# Input2.net
KiCad netlist of a schematic drawn in Altium Designer
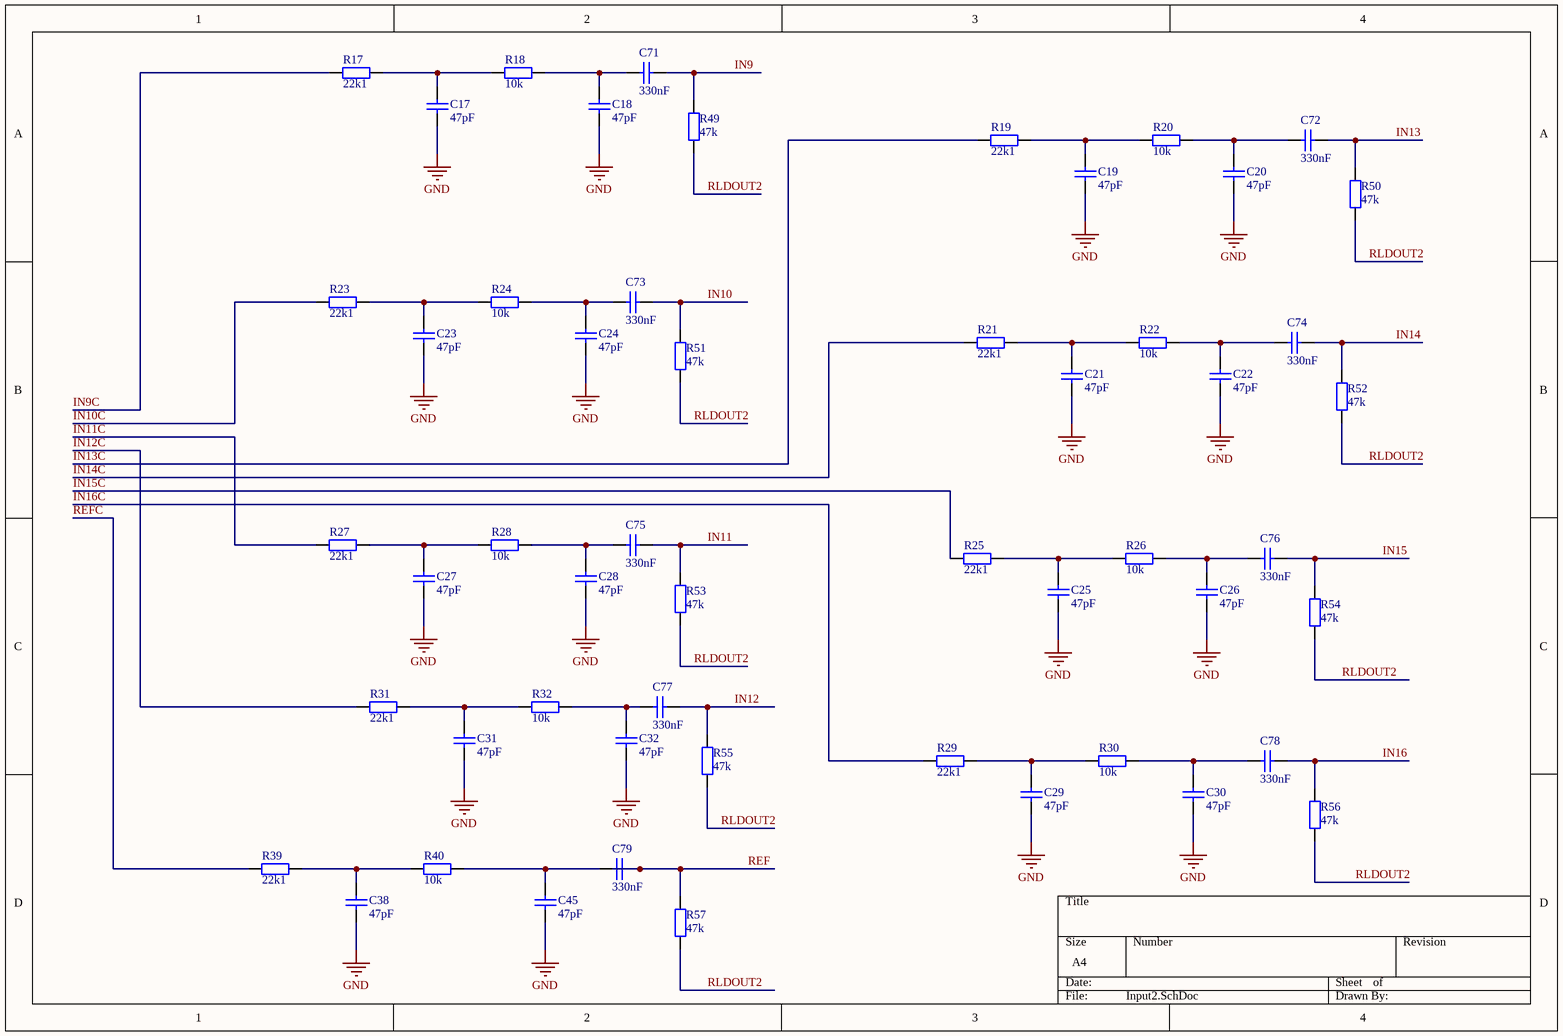
[diagram p0: Input2.SchDoc]

(export (version "E")
  (design (tool "Eeschema 10.0.6"))
  (components
    (comp (ref "C17")
      (value "47pF")
      (footprint "RESC1608X50N")
      (description "Capacitor")
      (fields (field (name "PUBLISHER") "Altium Limited"))
      (libsource (lib "Miscellaneous Devices") (part "Cap"))
    )
    (comp (ref "C18")
      (value "47pF")
      (footprint "RESC1608X50N")
      (description "Capacitor")
      (fields (field (name "PUBLISHER") "Altium Limited"))
      (libsource (lib "Miscellaneous Devices") (part "Cap"))
    )
    (comp (ref "C19")
      (value "47pF")
      (footprint "RESC1608X50N")
      (description "Capacitor")
      (fields (field (name "PUBLISHER") "Altium Limited"))
      (libsource (lib "Miscellaneous Devices") (part "Cap"))
    )
    (comp (ref "C20")
      (value "47pF")
      (footprint "RESC1608X50N")
      (description "Capacitor")
      (fields (field (name "PUBLISHER") "Altium Limited"))
      (libsource (lib "Miscellaneous Devices") (part "Cap"))
    )
    (comp (ref "C21")
      (value "47pF")
      (footprint "RESC1608X50N")
      (description "Capacitor")
      (fields (field (name "PUBLISHER") "Altium Limited"))
      (libsource (lib "Miscellaneous Devices") (part "Cap"))
    )
    (comp (ref "C22")
      (value "47pF")
      (footprint "RESC1608X50N")
      (description "Capacitor")
      (fields (field (name "PUBLISHER") "Altium Limited"))
      (libsource (lib "Miscellaneous Devices") (part "Cap"))
    )
    (comp (ref "C23")
      (value "47pF")
      (footprint "RESC1608X50N")
      (description "Capacitor")
      (fields (field (name "PUBLISHER") "Altium Limited"))
      (libsource (lib "Miscellaneous Devices") (part "Cap"))
    )
    (comp (ref "C24")
      (value "47pF")
      (footprint "RESC1608X50N")
      (description "Capacitor")
      (fields (field (name "PUBLISHER") "Altium Limited"))
      (libsource (lib "Miscellaneous Devices") (part "Cap"))
    )
    (comp (ref "C25")
      (value "47pF")
      (footprint "RESC1608X50N")
      (description "Capacitor")
      (fields (field (name "PUBLISHER") "Altium Limited"))
      (libsource (lib "Miscellaneous Devices") (part "Cap"))
    )
    (comp (ref "C26")
      (value "47pF")
      (footprint "RESC1608X50N")
      (description "Capacitor")
      (fields (field (name "PUBLISHER") "Altium Limited"))
      (libsource (lib "Miscellaneous Devices") (part "Cap"))
    )
    (comp (ref "C27")
      (value "47pF")
      (footprint "RESC1608X50N")
      (description "Capacitor")
      (fields (field (name "PUBLISHER") "Altium Limited"))
      (libsource (lib "Miscellaneous Devices") (part "Cap"))
    )
    (comp (ref "C28")
      (value "47pF")
      (footprint "RESC1608X50N")
      (description "Capacitor")
      (fields (field (name "PUBLISHER") "Altium Limited"))
      (libsource (lib "Miscellaneous Devices") (part "Cap"))
    )
    (comp (ref "C29")
      (value "47pF")
      (footprint "RESC1608X50N")
      (description "Capacitor")
      (fields (field (name "PUBLISHER") "Altium Limited"))
      (libsource (lib "Miscellaneous Devices") (part "Cap"))
    )
    (comp (ref "C30")
      (value "47pF")
      (footprint "RESC1608X50N")
      (description "Capacitor")
      (fields (field (name "PUBLISHER") "Altium Limited"))
      (libsource (lib "Miscellaneous Devices") (part "Cap"))
    )
    (comp (ref "C31")
      (value "47pF")
      (footprint "RESC1608X50N")
      (description "Capacitor")
      (fields (field (name "PUBLISHER") "Altium Limited"))
      (libsource (lib "Miscellaneous Devices") (part "Cap"))
    )
    (comp (ref "C32")
      (value "47pF")
      (footprint "RESC1608X50N")
      (description "Capacitor")
      (fields (field (name "PUBLISHER") "Altium Limited"))
      (libsource (lib "Miscellaneous Devices") (part "Cap"))
    )
    (comp (ref "C38")
      (value "47pF")
      (footprint "RESC1608X50N")
      (description "Capacitor")
      (fields (field (name "PUBLISHER") "Altium Limited"))
      (libsource (lib "Miscellaneous Devices") (part "Cap"))
    )
    (comp (ref "C45")
      (value "47pF")
      (footprint "RESC1608X50N")
      (description "Capacitor")
      (fields (field (name "PUBLISHER") "Altium Limited"))
      (libsource (lib "Miscellaneous Devices") (part "Cap"))
    )
    (comp (ref "C71")
      (value "330nF")
      (footprint "RESC1608X50N")
      (description "Capacitor")
      (fields (field (name "PUBLISHER") "Altium Limited"))
      (libsource (lib "Miscellaneous Devices") (part "Cap"))
    )
    (comp (ref "C72")
      (value "330nF")
      (footprint "RESC1608X50N")
      (description "Capacitor")
      (fields (field (name "PUBLISHER") "Altium Limited"))
      (libsource (lib "Miscellaneous Devices") (part "Cap"))
    )
    (comp (ref "C73")
      (value "330nF")
      (footprint "RESC1608X50N")
      (description "Capacitor")
      (fields (field (name "PUBLISHER") "Altium Limited"))
      (libsource (lib "Miscellaneous Devices") (part "Cap"))
    )
    (comp (ref "C74")
      (value "330nF")
      (footprint "RESC1608X50N")
      (description "Capacitor")
      (fields (field (name "PUBLISHER") "Altium Limited"))
      (libsource (lib "Miscellaneous Devices") (part "Cap"))
    )
    (comp (ref "C75")
      (value "330nF")
      (footprint "RESC1608X50N")
      (description "Capacitor")
      (fields (field (name "PUBLISHER") "Altium Limited"))
      (libsource (lib "Miscellaneous Devices") (part "Cap"))
    )
    (comp (ref "C76")
      (value "330nF")
      (footprint "RESC1608X50N")
      (description "Capacitor")
      (fields (field (name "PUBLISHER") "Altium Limited"))
      (libsource (lib "Miscellaneous Devices") (part "Cap"))
    )
    (comp (ref "C77")
      (value "330nF")
      (footprint "RESC1608X50N")
      (description "Capacitor")
      (fields (field (name "PUBLISHER") "Altium Limited"))
      (libsource (lib "Miscellaneous Devices") (part "Cap"))
    )
    (comp (ref "C78")
      (value "330nF")
      (footprint "RESC1608X50N")
      (description "Capacitor")
      (fields (field (name "PUBLISHER") "Altium Limited"))
      (libsource (lib "Miscellaneous Devices") (part "Cap"))
    )
    (comp (ref "C79")
      (value "330nF")
      (footprint "RESC1608X50N")
      (description "Capacitor")
      (fields (field (name "PUBLISHER") "Altium Limited"))
      (libsource (lib "Miscellaneous Devices") (part "Cap"))
    )
    (comp (ref "R17")
      (value "22k1")
      (footprint "CAPC1608X90")
      (description "Resistor")
      (fields (field (name "PUBLISHER") "Altium Limited"))
      (libsource (lib "") (part "Res2_1"))
    )
    (comp (ref "R18")
      (value "10k")
      (footprint "CAPC1608X90")
      (description "Resistor")
      (fields (field (name "PUBLISHER") "Altium Limited"))
      (libsource (lib "") (part "Res2_1"))
    )
    (comp (ref "R19")
      (value "22k1")
      (footprint "CAPC1608X90")
      (description "Resistor")
      (fields (field (name "PUBLISHER") "Altium Limited"))
      (libsource (lib "") (part "Res2_1"))
    )
    (comp (ref "R20")
      (value "10k")
      (footprint "CAPC1608X90")
      (description "Resistor")
      (fields (field (name "PUBLISHER") "Altium Limited"))
      (libsource (lib "") (part "Res2_1"))
    )
    (comp (ref "R21")
      (value "22k1")
      (footprint "CAPC1608X90")
      (description "Resistor")
      (fields (field (name "PUBLISHER") "Altium Limited"))
      (libsource (lib "") (part "Res2_1"))
    )
    (comp (ref "R22")
      (value "10k")
      (footprint "CAPC1608X90")
      (description "Resistor")
      (fields (field (name "PUBLISHER") "Altium Limited"))
      (libsource (lib "") (part "Res2_1"))
    )
    (comp (ref "R23")
      (value "22k1")
      (footprint "CAPC1608X90")
      (description "Resistor")
      (fields (field (name "PUBLISHER") "Altium Limited"))
      (libsource (lib "") (part "Res2_1"))
    )
    (comp (ref "R24")
      (value "10k")
      (footprint "CAPC1608X90")
      (description "Resistor")
      (fields (field (name "PUBLISHER") "Altium Limited"))
      (libsource (lib "") (part "Res2_1"))
    )
    (comp (ref "R25")
      (value "22k1")
      (footprint "CAPC1608X90")
      (description "Resistor")
      (fields (field (name "PUBLISHER") "Altium Limited"))
      (libsource (lib "") (part "Res2_1"))
    )
    (comp (ref "R26")
      (value "10k")
      (footprint "CAPC1608X90")
      (description "Resistor")
      (fields (field (name "PUBLISHER") "Altium Limited"))
      (libsource (lib "") (part "Res2_1"))
    )
    (comp (ref "R27")
      (value "22k1")
      (footprint "CAPC1608X90")
      (description "Resistor")
      (fields (field (name "PUBLISHER") "Altium Limited"))
      (libsource (lib "") (part "Res2_1"))
    )
    (comp (ref "R28")
      (value "10k")
      (footprint "CAPC1608X90")
      (description "Resistor")
      (fields (field (name "PUBLISHER") "Altium Limited"))
      (libsource (lib "") (part "Res2_1"))
    )
    (comp (ref "R29")
      (value "22k1")
      (footprint "CAPC1608X90")
      (description "Resistor")
      (fields (field (name "PUBLISHER") "Altium Limited"))
      (libsource (lib "") (part "Res2_1"))
    )
    (comp (ref "R30")
      (value "10k")
      (footprint "CAPC1608X90")
      (description "Resistor")
      (fields (field (name "PUBLISHER") "Altium Limited"))
      (libsource (lib "") (part "Res2_1"))
    )
    (comp (ref "R31")
      (value "22k1")
      (footprint "CAPC1608X90")
      (description "Resistor")
      (fields (field (name "PUBLISHER") "Altium Limited"))
      (libsource (lib "") (part "Res2_1"))
    )
    (comp (ref "R32")
      (value "10k")
      (footprint "CAPC1608X90")
      (description "Resistor")
      (fields (field (name "PUBLISHER") "Altium Limited"))
      (libsource (lib "") (part "Res2_1"))
    )
    (comp (ref "R39")
      (value "22k1")
      (footprint "CAPC1608X90")
      (description "Resistor")
      (fields (field (name "PUBLISHER") "Altium Limited"))
      (libsource (lib "") (part "Res2_1"))
    )
    (comp (ref "R40")
      (value "10k")
      (footprint "CAPC1608X90")
      (description "Resistor")
      (fields (field (name "PUBLISHER") "Altium Limited"))
      (libsource (lib "") (part "Res2_1"))
    )
    (comp (ref "R49")
      (value "47k")
      (footprint "CAPC1608X90")
      (description "Resistor")
      (fields (field (name "PUBLISHER") "Altium Limited"))
      (libsource (lib "Miscellaneous Devices") (part "Res2"))
    )
    (comp (ref "R50")
      (value "47k")
      (footprint "CAPC1608X90")
      (description "Resistor")
      (fields (field (name "PUBLISHER") "Altium Limited"))
      (libsource (lib "Miscellaneous Devices") (part "Res2"))
    )
    (comp (ref "R51")
      (value "47k")
      (footprint "CAPC1608X90")
      (description "Resistor")
      (fields (field (name "PUBLISHER") "Altium Limited"))
      (libsource (lib "Miscellaneous Devices") (part "Res2"))
    )
    (comp (ref "R52")
      (value "47k")
      (footprint "CAPC1608X90")
      (description "Resistor")
      (fields (field (name "PUBLISHER") "Altium Limited"))
      (libsource (lib "Miscellaneous Devices") (part "Res2"))
    )
    (comp (ref "R53")
      (value "47k")
      (footprint "CAPC1608X90")
      (description "Resistor")
      (fields (field (name "PUBLISHER") "Altium Limited"))
      (libsource (lib "Miscellaneous Devices") (part "Res2"))
    )
    (comp (ref "R54")
      (value "47k")
      (footprint "CAPC1608X90")
      (description "Resistor")
      (fields (field (name "PUBLISHER") "Altium Limited"))
      (libsource (lib "Miscellaneous Devices") (part "Res2"))
    )
    (comp (ref "R55")
      (value "47k")
      (footprint "CAPC1608X90")
      (description "Resistor")
      (fields (field (name "PUBLISHER") "Altium Limited"))
      (libsource (lib "Miscellaneous Devices") (part "Res2"))
    )
    (comp (ref "R56")
      (value "47k")
      (footprint "CAPC1608X90")
      (description "Resistor")
      (fields (field (name "PUBLISHER") "Altium Limited"))
      (libsource (lib "Miscellaneous Devices") (part "Res2"))
    )
    (comp (ref "R57")
      (value "47k")
      (footprint "CAPC1608X90")
      (description "Resistor")
      (fields (field (name "PUBLISHER") "Altium Limited"))
      (libsource (lib "Miscellaneous Devices") (part "Res2"))
    )
  )
  (nets
    (net (code "1") (name "/IN9") (class "Default")
      (node (ref "C71") (pin "1") (pinfunction "1_1") (pintype "passive"))
      (node (ref "R49") (pin "2") (pinfunction "2_2") (pintype "passive"))
    )
    (net (code "2") (name "/IN9C") (class "Default")
      (node (ref "R17") (pin "1") (pinfunction "1_1") (pintype "passive"))
    )
    (net (code "3") (name "/IN10") (class "Default")
      (node (ref "C73") (pin "1") (pinfunction "1_1") (pintype "passive"))
      (node (ref "R51") (pin "2") (pinfunction "2_2") (pintype "passive"))
    )
    (net (code "4") (name "/IN10C") (class "Default")
      (node (ref "R23") (pin "1") (pinfunction "1_1") (pintype "passive"))
    )
    (net (code "5") (name "/IN11") (class "Default")
      (node (ref "C75") (pin "1") (pinfunction "1_1") (pintype "passive"))
      (node (ref "R53") (pin "2") (pinfunction "2_2") (pintype "passive"))
    )
    (net (code "6") (name "/IN11C") (class "Default")
      (node (ref "R27") (pin "1") (pinfunction "1_1") (pintype "passive"))
    )
    (net (code "7") (name "/IN12") (class "Default")
      (node (ref "C77") (pin "1") (pinfunction "1_1") (pintype "passive"))
      (node (ref "R55") (pin "2") (pinfunction "2_2") (pintype "passive"))
    )
    (net (code "8") (name "/IN12C") (class "Default")
      (node (ref "R31") (pin "1") (pinfunction "1_1") (pintype "passive"))
    )
    (net (code "9") (name "/IN13") (class "Default")
      (node (ref "C72") (pin "1") (pinfunction "1_1") (pintype "passive"))
      (node (ref "R50") (pin "2") (pinfunction "2_2") (pintype "passive"))
    )
    (net (code "10") (name "/IN13C") (class "Default")
      (node (ref "R19") (pin "1") (pinfunction "1_1") (pintype "passive"))
    )
    (net (code "11") (name "/IN14") (class "Default")
      (node (ref "C74") (pin "1") (pinfunction "1_1") (pintype "passive"))
      (node (ref "R52") (pin "2") (pinfunction "2_2") (pintype "passive"))
    )
    (net (code "12") (name "/IN14C") (class "Default")
      (node (ref "R21") (pin "1") (pinfunction "1_1") (pintype "passive"))
    )
    (net (code "13") (name "/IN15") (class "Default")
      (node (ref "C76") (pin "1") (pinfunction "1_1") (pintype "passive"))
      (node (ref "R54") (pin "2") (pinfunction "2_2") (pintype "passive"))
    )
    (net (code "14") (name "/IN15C") (class "Default")
      (node (ref "R25") (pin "1") (pinfunction "1_1") (pintype "passive"))
    )
    (net (code "15") (name "/IN16") (class "Default")
      (node (ref "C78") (pin "1") (pinfunction "1_1") (pintype "passive"))
      (node (ref "R56") (pin "2") (pinfunction "2_2") (pintype "passive"))
    )
    (net (code "16") (name "/IN16C") (class "Default")
      (node (ref "R29") (pin "1") (pinfunction "1_1") (pintype "passive"))
    )
    (net (code "17") (name "/REF") (class "Default")
      (node (ref "C79") (pin "1") (pinfunction "1_1") (pintype "passive"))
      (node (ref "R57") (pin "2") (pinfunction "2_2") (pintype "passive"))
    )
    (net (code "18") (name "/REFC") (class "Default")
      (node (ref "R39") (pin "1") (pinfunction "1_1") (pintype "passive"))
    )
    (net (code "19") (name "/RLDOUT2") (class "Default")
      (node (ref "R49") (pin "1") (pinfunction "1_1") (pintype "passive"))
      (node (ref "R50") (pin "1") (pinfunction "1_1") (pintype "passive"))
      (node (ref "R51") (pin "1") (pinfunction "1_1") (pintype "passive"))
      (node (ref "R52") (pin "1") (pinfunction "1_1") (pintype "passive"))
      (node (ref "R53") (pin "1") (pinfunction "1_1") (pintype "passive"))
      (node (ref "R54") (pin "1") (pinfunction "1_1") (pintype "passive"))
      (node (ref "R55") (pin "1") (pinfunction "1_1") (pintype "passive"))
      (node (ref "R56") (pin "1") (pinfunction "1_1") (pintype "passive"))
      (node (ref "R57") (pin "1") (pinfunction "1_1") (pintype "passive"))
    )
    (net (code "20") (name "GND") (class "Default")
      (node (ref "C17") (pin "1") (pinfunction "1_1") (pintype "passive"))
      (node (ref "C18") (pin "1") (pinfunction "1_1") (pintype "passive"))
      (node (ref "C19") (pin "1") (pinfunction "1_1") (pintype "passive"))
      (node (ref "C20") (pin "1") (pinfunction "1_1") (pintype "passive"))
      (node (ref "C21") (pin "1") (pinfunction "1_1") (pintype "passive"))
      (node (ref "C22") (pin "1") (pinfunction "1_1") (pintype "passive"))
      (node (ref "C23") (pin "1") (pinfunction "1_1") (pintype "passive"))
      (node (ref "C24") (pin "1") (pinfunction "1_1") (pintype "passive"))
      (node (ref "C25") (pin "1") (pinfunction "1_1") (pintype "passive"))
      (node (ref "C26") (pin "1") (pinfunction "1_1") (pintype "passive"))
      (node (ref "C27") (pin "1") (pinfunction "1_1") (pintype "passive"))
      (node (ref "C28") (pin "1") (pinfunction "1_1") (pintype "passive"))
      (node (ref "C29") (pin "1") (pinfunction "1_1") (pintype "passive"))
      (node (ref "C30") (pin "1") (pinfunction "1_1") (pintype "passive"))
      (node (ref "C31") (pin "1") (pinfunction "1_1") (pintype "passive"))
      (node (ref "C32") (pin "1") (pinfunction "1_1") (pintype "passive"))
      (node (ref "C38") (pin "1") (pinfunction "1_1") (pintype "passive"))
      (node (ref "C45") (pin "1") (pinfunction "1_1") (pintype "passive"))
    )
    (net (code "21") (name "Net-(C17-Pad2)") (class "Default")
      (node (ref "C17") (pin "2") (pinfunction "2_2") (pintype "passive"))
      (node (ref "R17") (pin "2") (pinfunction "2_2") (pintype "passive"))
      (node (ref "R18") (pin "1") (pinfunction "1_1") (pintype "passive"))
    )
    (net (code "22") (name "Net-(C18-Pad2)") (class "Default")
      (node (ref "C18") (pin "2") (pinfunction "2_2") (pintype "passive"))
      (node (ref "C71") (pin "2") (pinfunction "2_2") (pintype "passive"))
      (node (ref "R18") (pin "2") (pinfunction "2_2") (pintype "passive"))
    )
    (net (code "23") (name "Net-(C19-Pad2)") (class "Default")
      (node (ref "C19") (pin "2") (pinfunction "2_2") (pintype "passive"))
      (node (ref "R19") (pin "2") (pinfunction "2_2") (pintype "passive"))
      (node (ref "R20") (pin "1") (pinfunction "1_1") (pintype "passive"))
    )
    (net (code "24") (name "Net-(C20-Pad2)") (class "Default")
      (node (ref "C20") (pin "2") (pinfunction "2_2") (pintype "passive"))
      (node (ref "C72") (pin "2") (pinfunction "2_2") (pintype "passive"))
      (node (ref "R20") (pin "2") (pinfunction "2_2") (pintype "passive"))
    )
    (net (code "25") (name "Net-(C21-Pad2)") (class "Default")
      (node (ref "C21") (pin "2") (pinfunction "2_2") (pintype "passive"))
      (node (ref "R21") (pin "2") (pinfunction "2_2") (pintype "passive"))
      (node (ref "R22") (pin "1") (pinfunction "1_1") (pintype "passive"))
    )
    (net (code "26") (name "Net-(C22-Pad2)") (class "Default")
      (node (ref "C22") (pin "2") (pinfunction "2_2") (pintype "passive"))
      (node (ref "C74") (pin "2") (pinfunction "2_2") (pintype "passive"))
      (node (ref "R22") (pin "2") (pinfunction "2_2") (pintype "passive"))
    )
    (net (code "27") (name "Net-(C23-Pad2)") (class "Default")
      (node (ref "C23") (pin "2") (pinfunction "2_2") (pintype "passive"))
      (node (ref "R23") (pin "2") (pinfunction "2_2") (pintype "passive"))
      (node (ref "R24") (pin "1") (pinfunction "1_1") (pintype "passive"))
    )
    (net (code "28") (name "Net-(C24-Pad2)") (class "Default")
      (node (ref "C24") (pin "2") (pinfunction "2_2") (pintype "passive"))
      (node (ref "C73") (pin "2") (pinfunction "2_2") (pintype "passive"))
      (node (ref "R24") (pin "2") (pinfunction "2_2") (pintype "passive"))
    )
    (net (code "29") (name "Net-(C25-Pad2)") (class "Default")
      (node (ref "C25") (pin "2") (pinfunction "2_2") (pintype "passive"))
      (node (ref "R25") (pin "2") (pinfunction "2_2") (pintype "passive"))
      (node (ref "R26") (pin "1") (pinfunction "1_1") (pintype "passive"))
    )
    (net (code "30") (name "Net-(C26-Pad2)") (class "Default")
      (node (ref "C26") (pin "2") (pinfunction "2_2") (pintype "passive"))
      (node (ref "C76") (pin "2") (pinfunction "2_2") (pintype "passive"))
      (node (ref "R26") (pin "2") (pinfunction "2_2") (pintype "passive"))
    )
    (net (code "31") (name "Net-(C27-Pad2)") (class "Default")
      (node (ref "C27") (pin "2") (pinfunction "2_2") (pintype "passive"))
      (node (ref "R27") (pin "2") (pinfunction "2_2") (pintype "passive"))
      (node (ref "R28") (pin "1") (pinfunction "1_1") (pintype "passive"))
    )
    (net (code "32") (name "Net-(C28-Pad2)") (class "Default")
      (node (ref "C28") (pin "2") (pinfunction "2_2") (pintype "passive"))
      (node (ref "C75") (pin "2") (pinfunction "2_2") (pintype "passive"))
      (node (ref "R28") (pin "2") (pinfunction "2_2") (pintype "passive"))
    )
    (net (code "33") (name "Net-(C29-Pad2)") (class "Default")
      (node (ref "C29") (pin "2") (pinfunction "2_2") (pintype "passive"))
      (node (ref "R29") (pin "2") (pinfunction "2_2") (pintype "passive"))
      (node (ref "R30") (pin "1") (pinfunction "1_1") (pintype "passive"))
    )
    (net (code "34") (name "Net-(C30-Pad2)") (class "Default")
      (node (ref "C30") (pin "2") (pinfunction "2_2") (pintype "passive"))
      (node (ref "C78") (pin "2") (pinfunction "2_2") (pintype "passive"))
      (node (ref "R30") (pin "2") (pinfunction "2_2") (pintype "passive"))
    )
    (net (code "35") (name "Net-(C31-Pad2)") (class "Default")
      (node (ref "C31") (pin "2") (pinfunction "2_2") (pintype "passive"))
      (node (ref "R31") (pin "2") (pinfunction "2_2") (pintype "passive"))
      (node (ref "R32") (pin "1") (pinfunction "1_1") (pintype "passive"))
    )
    (net (code "36") (name "Net-(C32-Pad2)") (class "Default")
      (node (ref "C32") (pin "2") (pinfunction "2_2") (pintype "passive"))
      (node (ref "C77") (pin "2") (pinfunction "2_2") (pintype "passive"))
      (node (ref "R32") (pin "2") (pinfunction "2_2") (pintype "passive"))
    )
    (net (code "37") (name "Net-(C38-Pad2)") (class "Default")
      (node (ref "C38") (pin "2") (pinfunction "2_2") (pintype "passive"))
      (node (ref "R39") (pin "2") (pinfunction "2_2") (pintype "passive"))
      (node (ref "R40") (pin "1") (pinfunction "1_1") (pintype "passive"))
    )
    (net (code "38") (name "Net-(C45-Pad2)") (class "Default")
      (node (ref "C45") (pin "2") (pinfunction "2_2") (pintype "passive"))
      (node (ref "C79") (pin "2") (pinfunction "2_2") (pintype "passive"))
      (node (ref "R40") (pin "2") (pinfunction "2_2") (pintype "passive"))
    )
  )
)
